# boost_ematik.net
KiCad netlist of a schematic drawn in Altium Designer
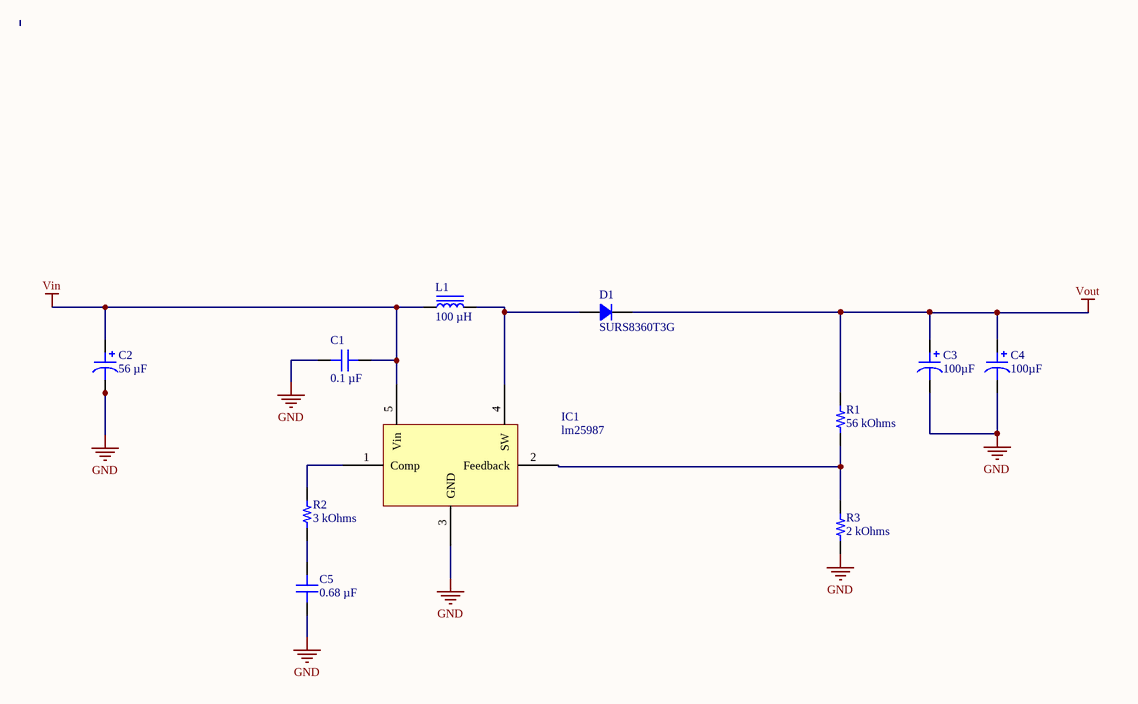
[diagram p0: boost şematik.SchDoc]

(export (version "E")
  (design (tool "Eeschema 10.0.6"))
  (components
    (comp (ref "C1")
      (value "0.1 µF")
      (footprint "CAP 0805_2012")
      (description "CAP CER 0.1UF 50V X7R 0805")
      (fields (field (name "PART NUMBER") "CC0805MRX7R9BB104") (field (name "MANUFACTURER") "Yageo"))
      (libsource (lib "Celestial Altium Library - altium_library") (part "Capacitor"))
    )
    (comp (ref "C2")
      (value "56 µF")
      (footprint "CAP ALSMD 6.6MM H7.7MM")
      (description "CAP ALUM 56UF 20% 35V SMD")
      (fields (field (name "PART NUMBER") "UUD1V560MCL1GS") (field (name "MANUFACTURER") "Nichicon"))
      (libsource (lib "Celestial Altium Library - altium_library") (part "Polarised Capacitor"))
    )
    (comp (ref "C3")
      (value "100µF")
      (footprint "CAP ALSMD 8.3MM H10.5MM")
      (description "CAP ALUM 100UF 20% 50V SMD")
      (fields
        (field (name "PART NUMBER") "EEE-FK1H101P")
        (field (name "MANUFACTURER") "Panasonic Electronic Components")
      )
      (libsource (lib "Celestial Altium Library - altium_library") (part "Polarised Capacitor"))
    )
    (comp (ref "C4")
      (value "100µF")
      (footprint "CAP ALSMD 8.3MM H10.5MM")
      (description "CAP ALUM 100UF 20% 50V SMD")
      (fields
        (field (name "PART NUMBER") "EEE-FK1H101P")
        (field (name "MANUFACTURER") "Panasonic Electronic Components")
      )
      (libsource (lib "Celestial Altium Library - altium_library") (part "Polarised Capacitor"))
    )
    (comp (ref "C5")
      (value "0.68 µF")
      (footprint "CAP 0805_2012")
      (description "CAP CER 0.68UF 50V X7R 0805")
      (fields (field (name "PART NUMBER") "C0805C684K5RACAUTO") (field (name "MANUFACTURER") "KEMET"))
      (libsource (lib "Celestial Altium Library - altium_library") (part "Capacitor"))
    )
    (comp (ref "D1")
      (value "SURS8360T3G")
      (footprint "DO214AB SMC")
      (description "DIODE GEN PURP 600V 3A SMC")
      (fields (field (name "MANUFACTURER") "ON Semiconductor"))
      (libsource (lib "Celestial Altium Library - altium_library") (part "Diode"))
    )
    (comp (ref "IC1")
      (value "lm25987")
      (footprint "LM2587 FOOTPRİNT:LM2596 FOOTPRİNT")
      (libsource (lib "lm2587 sembol") (part "lm25987"))
    )
    (comp (ref "L1")
      (value "100 µH")
      (footprint "LM2587 FOOTPRİNT:7447070 bobin")
      (description "FIXED IND 100UH 2.1A 150MOHM SMD")
      (fields (field (name "PART NUMBER") "SRR1280-101M") (field (name "MANUFACTURER") "Bourns Inc."))
      (libsource (lib "Celestial Altium Library - altium_library") (part "Inductor"))
    )
    (comp (ref "R1")
      (value "56 kOhms")
      (footprint "RES 0805_2012")
      (description "RES 56K OHM 0.5% 1/8W 0805")
      (fields
        (field (name "PART NUMBER") "RNCF0805DTE56K0")
        (field (name "MANUFACTURER") "Stackpole Electronics Inc")
      )
      (libsource (lib "Celestial Altium Library - altium_library") (part "Resistor"))
    )
    (comp (ref "R2")
      (value "3 kOhms")
      (footprint "RES 0805_2012")
      (description "RES SMD 3K OHM 1% 1/8W 0805")
      (fields (field (name "PART NUMBER") "AC0805FR-073KL") (field (name "MANUFACTURER") "Yageo"))
      (libsource (lib "Celestial Altium Library - altium_library") (part "Resistor"))
    )
    (comp (ref "R3")
      (value "2 kOhms")
      (footprint "RES 0805_2012")
      (description "RES SMD 2K OHM 1% 1/8W 0805")
      (fields (field (name "PART NUMBER") "AC0805FR-072KL") (field (name "MANUFACTURER") "Yageo"))
      (libsource (lib "Celestial Altium Library - altium_library") (part "Resistor"))
    )
  )
  (nets
    (net (code "1") (name "GND") (class "Default")
      (node (ref "C1") (pin "2") (pinfunction "2_2") (pintype "passive"))
      (node (ref "C2") (pin "2") (pinfunction "2_2") (pintype "passive"))
      (node (ref "C3") (pin "2") (pinfunction "2_2") (pintype "passive"))
      (node (ref "C4") (pin "2") (pinfunction "2_2") (pintype "passive"))
      (node (ref "C5") (pin "1") (pinfunction "1_1") (pintype "passive"))
      (node (ref "IC1") (pin "3") (pinfunction "GND_3") (pintype "passive"))
      (node (ref "R3") (pin "1") (pinfunction "1_1") (pintype "passive"))
    )
    (net (code "2") (name "Net-(C5-Pad2)") (class "Default")
      (node (ref "C5") (pin "2") (pinfunction "2_2") (pintype "passive"))
      (node (ref "R2") (pin "1") (pinfunction "1_1") (pintype "passive"))
    )
    (net (code "3") (name "Net-(IC1-Comp)") (class "Default")
      (node (ref "IC1") (pin "1") (pinfunction "Comp_1") (pintype "passive"))
      (node (ref "R2") (pin "2") (pinfunction "2_2") (pintype "passive"))
    )
    (net (code "4") (name "Net-(IC1-Feedback)") (class "Default")
      (node (ref "IC1") (pin "2") (pinfunction "Feedback_2") (pintype "passive"))
      (node (ref "R1") (pin "1") (pinfunction "1_1") (pintype "passive"))
      (node (ref "R3") (pin "2") (pinfunction "2_2") (pintype "passive"))
    )
    (net (code "5") (name "Net-(IC1-SW)") (class "Default")
      (node (ref "D1") (pin "1") (pinfunction "1_1") (pintype "passive"))
      (node (ref "IC1") (pin "4") (pinfunction "SW_4") (pintype "passive"))
      (node (ref "L1") (pin "2") (pinfunction "2_2") (pintype "passive"))
    )
    (net (code "6") (name "Vin") (class "Default")
      (node (ref "C1") (pin "1") (pinfunction "1_1") (pintype "passive"))
      (node (ref "C2") (pin "1") (pinfunction "1_1") (pintype "passive"))
      (node (ref "IC1") (pin "5") (pinfunction "Vin_5") (pintype "passive"))
      (node (ref "L1") (pin "1") (pinfunction "1_1") (pintype "passive"))
    )
    (net (code "7") (name "Vout") (class "Default")
      (node (ref "C3") (pin "1") (pinfunction "1_1") (pintype "passive"))
      (node (ref "C4") (pin "1") (pinfunction "1_1") (pintype "passive"))
      (node (ref "D1") (pin "2") (pinfunction "2_2") (pintype "passive"))
      (node (ref "R1") (pin "2") (pinfunction "2_2") (pintype "passive"))
    )
  )
)
